# DoorCard.net
KiCad netlist of a schematic drawn in Altium Designer
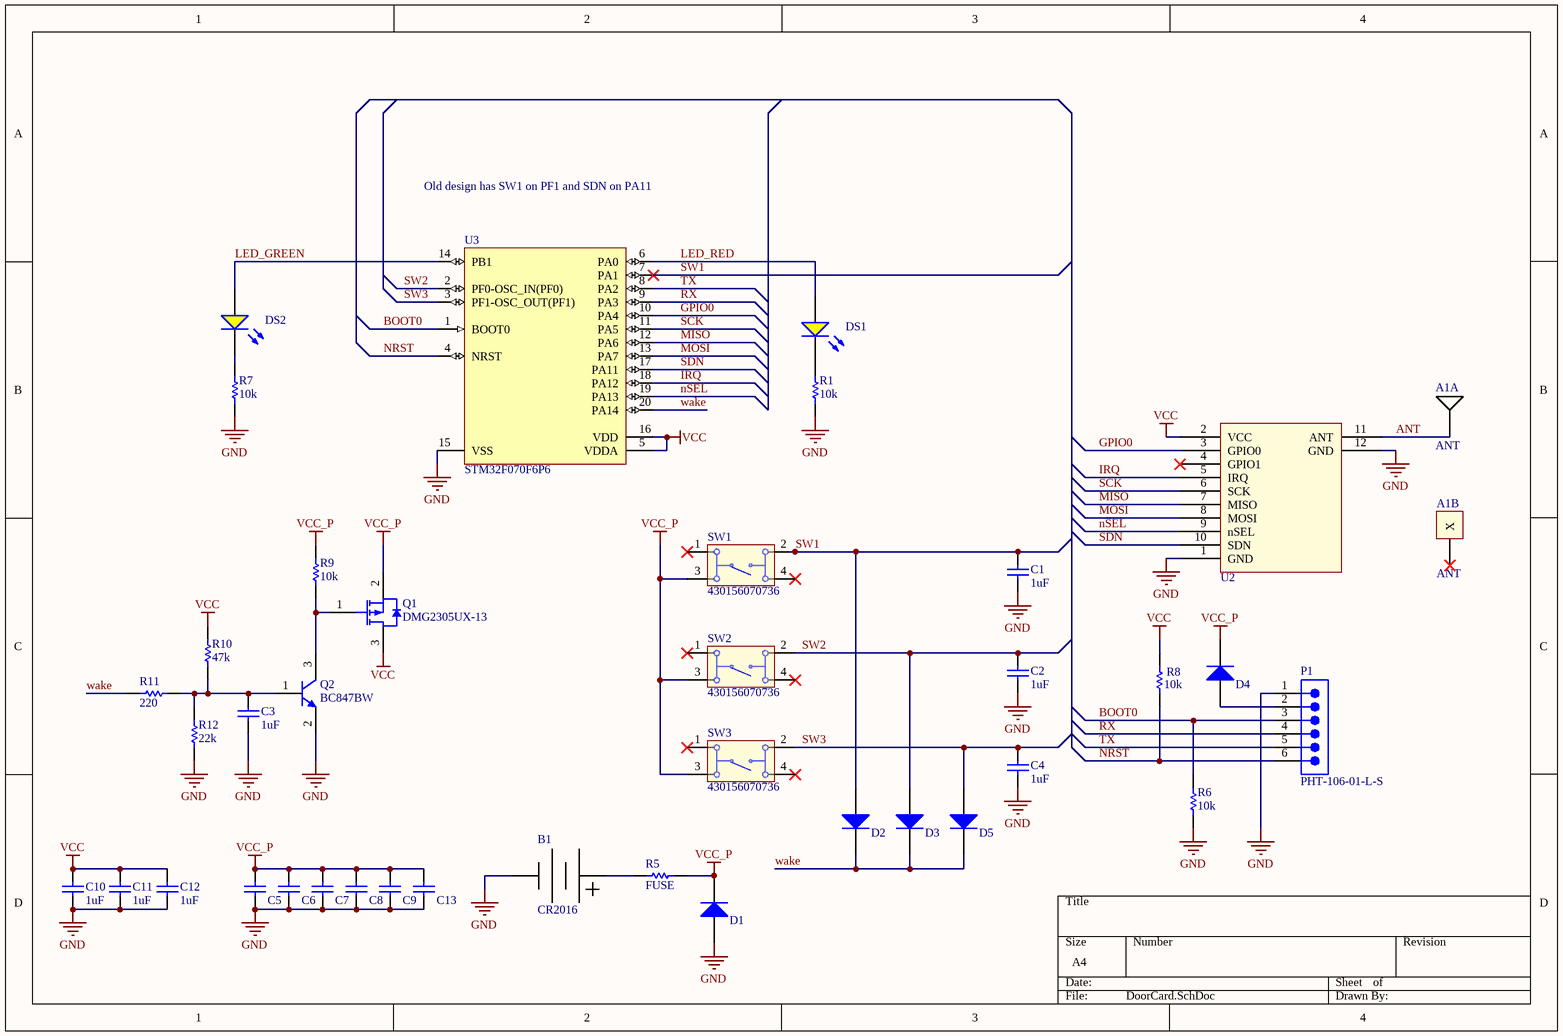
[diagram p0: DoorCard.SchDoc]

(export (version "E")
  (design (tool "Eeschema 10.0.6"))
  (components
    (comp (ref "A1")
      (value "ANT")
      (footprint "433MHz_Antenna")
      (description "ANT1204F002R0433A")
      (libsource (lib "Antenna") (part "ANT1204F002R0433A"))
    )
    (comp (ref "B1")
      (value "CR2016")
      (footprint "CR2012")
      (description "BAT-HLD-002-SMT")
      (libsource (lib "Cell") (part "BAT-HLD-002-SMT"))
    )
    (comp (ref "C1")
      (value "1uF")
      (footprint "CAPC0805(2012)100_M")
      (description "CAP 1uF 25V ±10% 0805 (2012 Metric) Thickness 1mm SMD")
      (fields (field (name "TOLERANCE") "Â±10%"))
      (libsource (lib "Altium Content Vault") (part "CAP"))
    )
    (comp (ref "C2")
      (value "1uF")
      (footprint "CAPC0805(2012)100_M")
      (description "CAP 1uF 25V ±10% 0805 (2012 Metric) Thickness 1mm SMD")
      (fields (field (name "TOLERANCE") "Â±10%"))
      (libsource (lib "Altium Content Vault") (part "CAP"))
    )
    (comp (ref "C3")
      (value "1uF")
      (footprint "CAPC0805(2012)100_M")
      (description "CAP 1uF 25V ±10% 0805 (2012 Metric) Thickness 1mm SMD")
      (fields (field (name "TOLERANCE") "Â±10%"))
      (libsource (lib "Altium Content Vault") (part "CAP"))
    )
    (comp (ref "C4")
      (value "1uF")
      (footprint "CAPC0805(2012)100_M")
      (description "CAP 1uF 25V ±10% 0805 (2012 Metric) Thickness 1mm SMD")
      (fields (field (name "TOLERANCE") "Â±10%"))
      (libsource (lib "Altium Content Vault") (part "CAP"))
    )
    (comp (ref "C5")
      (value "CAP 47uF 6.3V 1206(3216)")
      (footprint "CAPC1206(3216)190_M")
      (description "CAP 47uF 6.3V ±20% 1206 (3216 Metric) Thickness 1.9mm SMD")
      (fields (field (name "TOLERANCE") "Â±20%"))
      (libsource (lib "Altium Content Vault") (part "CMP-1037-05000-1"))
    )
    (comp (ref "C6")
      (value "CAP 47uF 6.3V 1206(3216)")
      (footprint "CAPC1206(3216)190_M")
      (description "CAP 47uF 6.3V ±20% 1206 (3216 Metric) Thickness 1.9mm SMD")
      (fields (field (name "TOLERANCE") "Â±20%"))
      (libsource (lib "Altium Content Vault") (part "CMP-1037-05000-1"))
    )
    (comp (ref "C7")
      (value "CAP 47uF 6.3V 1206(3216)")
      (footprint "CAPC1206(3216)190_M")
      (description "CAP 47uF 6.3V ±20% 1206 (3216 Metric) Thickness 1.9mm SMD")
      (fields (field (name "TOLERANCE") "Â±20%"))
      (libsource (lib "Altium Content Vault") (part "CMP-1037-05000-1"))
    )
    (comp (ref "C8")
      (value "CAP 47uF 6.3V 1206(3216)")
      (footprint "CAPC1206(3216)190_M")
      (description "CAP 47uF 6.3V ±20% 1206 (3216 Metric) Thickness 1.9mm SMD")
      (fields (field (name "TOLERANCE") "Â±20%"))
      (libsource (lib "Altium Content Vault") (part "CMP-1037-05000-1"))
    )
    (comp (ref "C9")
      (value "CAP 47uF 6.3V 1206(3216)")
      (footprint "CAPC1206(3216)190_M")
      (description "CAP 47uF 6.3V ±20% 1206 (3216 Metric) Thickness 1.9mm SMD")
      (fields (field (name "TOLERANCE") "Â±20%"))
      (libsource (lib "Altium Content Vault") (part "CMP-1037-05000-1"))
    )
    (comp (ref "C10")
      (value "1uF")
      (footprint "CAPC0805(2012)100_M")
      (description "CAP 1uF 25V ±10% 0805 (2012 Metric) Thickness 1mm SMD")
      (fields (field (name "TOLERANCE") "Â±10%"))
      (libsource (lib "Altium Content Vault") (part "CAP"))
    )
    (comp (ref "C11")
      (value "1uF")
      (footprint "CAPC0805(2012)100_M")
      (description "CAP 1uF 25V ±10% 0805 (2012 Metric) Thickness 1mm SMD")
      (fields (field (name "TOLERANCE") "Â±10%"))
      (libsource (lib "Altium Content Vault") (part "CAP"))
    )
    (comp (ref "C12")
      (value "1uF")
      (footprint "CAPC0805(2012)100_M")
      (description "CAP 1uF 25V ±10% 0805 (2012 Metric) Thickness 1mm SMD")
      (fields (field (name "TOLERANCE") "Â±10%"))
      (libsource (lib "Altium Content Vault") (part "CAP"))
    )
    (comp (ref "C13")
      (value "CAP 47uF 6.3V 1206(3216)")
      (footprint "CAPC1206(3216)190_M")
      (description "CAP 47uF 6.3V ±20% 1206 (3216 Metric) Thickness 1.9mm SMD")
      (fields (field (name "TOLERANCE") "Â±20%"))
      (libsource (lib "Altium Content Vault") (part "CMP-1037-05000-1"))
    )
    (comp (ref "D1")
      (value "MMSD4148T3G")
      (footprint "ONSC-SOD123-2-425G-04_V")
      (description "Switching Diode, 100 V, 200 mA, -55 to 150 degC, 2-Pin SOD123 (425), RoHS, Tape and Reel")
      (fields (field (name "MANUFACTURER") "ON Semiconductor"))
      (libsource (lib "Altium Content Vault") (part "ONSC-MMSD4148-SOD123-2"))
    )
    (comp (ref "D2")
      (value "MMSD4148T3G")
      (footprint "ONSC-SOD123-2-425G-04_V")
      (description "Switching Diode, 100 V, 200 mA, -55 to 150 degC, 2-Pin SOD123 (425), RoHS, Tape and Reel")
      (fields (field (name "MANUFACTURER") "ON Semiconductor"))
      (libsource (lib "Altium Content Vault") (part "ONSC-MMSD4148-SOD123-2"))
    )
    (comp (ref "D3")
      (value "MMSD4148T3G")
      (footprint "ONSC-SOD123-2-425G-04_V")
      (description "Switching Diode, 100 V, 200 mA, -55 to 150 degC, 2-Pin SOD123 (425), RoHS, Tape and Reel")
      (fields (field (name "MANUFACTURER") "ON Semiconductor"))
      (libsource (lib "Altium Content Vault") (part "ONSC-MMSD4148-SOD123-2"))
    )
    (comp (ref "D4")
      (value "MMSD4148T3G")
      (footprint "ONSC-SOD123-2-425G-04_V")
      (description "Switching Diode, 100 V, 200 mA, -55 to 150 degC, 2-Pin SOD123 (425), RoHS, Tape and Reel")
      (fields (field (name "MANUFACTURER") "ON Semiconductor"))
      (libsource (lib "Altium Content Vault") (part "ONSC-MMSD4148-SOD123-2"))
    )
    (comp (ref "D5")
      (value "MMSD4148T3G")
      (footprint "ONSC-SOD123-2-425G-04_V")
      (description "Switching Diode, 100 V, 200 mA, -55 to 150 degC, 2-Pin SOD123 (425), RoHS, Tape and Reel")
      (fields (field (name "MANUFACTURER") "ON Semiconductor"))
      (libsource (lib "Altium Content Vault") (part "ONSC-MMSD4148-SOD123-2"))
    )
    (comp (ref "DS1")
      (value "LTST-C170YKT")
      (footprint "LTST-C170YKT_V")
      (description "LED YELLOW CLEAR 0805 SMD")
      (libsource (lib "Altium Content Vault") (part "LED_YELLOW_AC"))
    )
    (comp (ref "DS2")
      (value "LTST-C170YKT")
      (footprint "LTST-C170YKT_V")
      (description "LED YELLOW CLEAR 0805 SMD")
      (libsource (lib "Altium Content Vault") (part "LED_YELLOW_AC"))
    )
    (comp (ref "P1")
      (value "PHT-106-01-L-S")
      (footprint "SMTC-PHT-106-01-X-S")
      (description "Press Fit Header, Through-hole, Vertical, -55 to 125 degC, 2.54 mm Pitch, 6-Pin, Male, RoHS")
      (fields (field (name "MANUFACTURER") "Samtec"))
      (libsource (lib "Altium Content Vault") (part "SMTC-PHT-106-01-X-S"))
    )
    (comp (ref "Q1")
      (value "DMG2305UX-13")
      (footprint "FAIR-SOT23-3_V")
      (fields (field (name "TOLERANCE") "30ppm"))
      (libsource (lib "Altium Content Vault") (part "PEMOS-GSD-3"))
    )
    (comp (ref "Q2")
      (value "BC847BW")
      (footprint "INF-SOT323_N")
      (description "NPN Silicon AF Transistor, 45 V VCEO, 100 mA IC, SOT323, Reel, Green")
      (fields (field (name "MANUFACTURER") "Infineon"))
      (libsource (lib "Altium Content Vault") (part "INF-BJTNPN-BEC-3"))
    )
    (comp (ref "R1")
      (value "10k")
      (footprint "RESC0805(2012)_L")
      (description "10K2 0.125W 1% 0805 (2012 Metric)  SMD")
      (fields (field (name "TOLERANCE") "1 %") (field (name "POWER") "0.125 W"))
      (libsource (lib "Altium Content Vault") (part "RES"))
    )
    (comp (ref "R5")
      (value "FUSE")
      (footprint "RESC0805(2012)_L")
      (description "PTC Fuse")
      (fields (field (name "TOLERANCE") "1 %") (field (name "POWER") "0.125 W"))
      (libsource (lib "Altium Content Vault") (part "RES"))
    )
    (comp (ref "R6")
      (value "10k")
      (footprint "RESC0805(2012)_L")
      (description "10K2 0.125W 1% 0805 (2012 Metric)  SMD")
      (fields (field (name "TOLERANCE") "1 %") (field (name "POWER") "0.125 W"))
      (libsource (lib "Altium Content Vault") (part "RES"))
    )
    (comp (ref "R7")
      (value "10k")
      (footprint "RESC0805(2012)_L")
      (description "10K2 0.125W 1% 0805 (2012 Metric)  SMD")
      (fields (field (name "TOLERANCE") "1 %") (field (name "POWER") "0.125 W"))
      (libsource (lib "Altium Content Vault") (part "RES"))
    )
    (comp (ref "R8")
      (value "10k")
      (footprint "RESC0805(2012)_L")
      (description "10K2 0.125W 1% 0805 (2012 Metric)  SMD")
      (fields (field (name "TOLERANCE") "1 %") (field (name "POWER") "0.125 W"))
      (libsource (lib "Altium Content Vault") (part "RES"))
    )
    (comp (ref "R9")
      (value "10k")
      (footprint "RESC0805(2012)_L")
      (description "10K2 0.125W 1% 0805 (2012 Metric)  SMD")
      (fields (field (name "TOLERANCE") "1 %") (field (name "POWER") "0.125 W"))
      (libsource (lib "Altium Content Vault") (part "RES"))
    )
    (comp (ref "R10")
      (value "47k")
      (footprint "RESC0805(2012)_L")
      (description "10K2 0.125W 1% 0805 (2012 Metric)  SMD")
      (fields (field (name "TOLERANCE") "1 %") (field (name "POWER") "0.125 W"))
      (libsource (lib "Altium Content Vault") (part "RES"))
    )
    (comp (ref "R11")
      (value "220")
      (footprint "RESC0805(2012)_L")
      (description "10K2 0.125W 1% 0805 (2012 Metric)  SMD")
      (fields (field (name "TOLERANCE") "1 %") (field (name "POWER") "0.125 W"))
      (libsource (lib "Altium Content Vault") (part "RES"))
    )
    (comp (ref "R12")
      (value "22k")
      (footprint "RESC0805(2012)_L")
      (description "10K2 0.125W 1% 0805 (2012 Metric)  SMD")
      (fields (field (name "TOLERANCE") "1 %") (field (name "POWER") "0.125 W"))
      (libsource (lib "Altium Content Vault") (part "RES"))
    )
    (comp (ref "SW1")
      (value "430156070736")
      (footprint "430156070736")
      (description "WS-TATV THT Tact Switch 6X6 mm")
      (fields (field (name "MANUFACTURER") "Wuerth Elektronik"))
      (libsource (lib "Altium Content Vault") (part "WE-TACT-SW-4"))
    )
    (comp (ref "SW2")
      (value "430156070736")
      (footprint "430156070736")
      (description "WS-TATV THT Tact Switch 6X6 mm")
      (fields (field (name "MANUFACTURER") "Wuerth Elektronik"))
      (libsource (lib "Altium Content Vault") (part "WE-TACT-SW-4"))
    )
    (comp (ref "SW3")
      (value "430156070736")
      (footprint "430156070736")
      (description "WS-TATV THT Tact Switch 6X6 mm")
      (fields (field (name "MANUFACTURER") "Wuerth Elektronik"))
      (libsource (lib "Altium Content Vault") (part "WE-TACT-SW-4"))
    )
    (comp (ref "U2")
      (value "Si4463")
      (footprint "E10-433MS")
      (description "E10-433MS")
      (libsource (lib "SiliconLabs") (part "Component_1"))
    )
    (comp (ref "U3")
      (value "STM32F070F6P6")
      (footprint "STM-TSSOP20_M")
      (fields (field (name "MANUFACTURER") "STMicroelectronics"))
      (libsource (lib "Altium Content Vault") (part "MC-ARM-STM32F070-TSSOP20"))
    )
  )
  (nets
    (net (code "1") (name "/ANT") (class "Default")
      (node (ref "A1") (pin "1") (pinfunction "ANT_1") (pintype "passive"))
      (node (ref "U2") (pin "11") (pinfunction "ANT_11") (pintype "passive"))
    )
    (net (code "2") (name "/BOOT0") (class "Default")
      (node (ref "P1") (pin "3") (pinfunction "3_3") (pintype "passive"))
      (node (ref "R6") (pin "2") (pinfunction "2_2") (pintype "passive"))
      (node (ref "U3") (pin "1") (pinfunction "BOOT0_1") (pintype "input"))
    )
    (net (code "3") (name "/GPIO0") (class "Default")
      (node (ref "U2") (pin "3") (pinfunction "GPIO0_3") (pintype "passive"))
      (node (ref "U3") (pin "10") (pinfunction "PA4_10") (pintype "bidirectional"))
    )
    (net (code "4") (name "/IRQ") (class "Default")
      (node (ref "U2") (pin "5") (pinfunction "IRQ_5") (pintype "passive"))
      (node (ref "U3") (pin "18") (pinfunction "PA12_18") (pintype "bidirectional"))
    )
    (net (code "5") (name "/LED_GREEN") (class "Default")
      (node (ref "DS2") (pin "A") (pinfunction "A_A") (pintype "passive"))
      (node (ref "U3") (pin "14") (pinfunction "PB1_14") (pintype "bidirectional"))
    )
    (net (code "6") (name "/LED_RED") (class "Default")
      (node (ref "DS1") (pin "A") (pinfunction "A_A") (pintype "passive"))
      (node (ref "U3") (pin "6") (pinfunction "PA0_6") (pintype "bidirectional"))
    )
    (net (code "7") (name "/MISO") (class "Default")
      (node (ref "U2") (pin "7") (pinfunction "MISO_7") (pintype "passive"))
      (node (ref "U3") (pin "12") (pinfunction "PA6_12") (pintype "bidirectional"))
    )
    (net (code "8") (name "/MOSI") (class "Default")
      (node (ref "U2") (pin "8") (pinfunction "MOSI_8") (pintype "passive"))
      (node (ref "U3") (pin "13") (pinfunction "PA7_13") (pintype "bidirectional"))
    )
    (net (code "9") (name "/NRST") (class "Default")
      (node (ref "P1") (pin "6") (pinfunction "6_6") (pintype "passive"))
      (node (ref "R8") (pin "1") (pinfunction "1_1") (pintype "passive"))
      (node (ref "U3") (pin "4") (pinfunction "NRST_4") (pintype "bidirectional"))
    )
    (net (code "10") (name "/RX") (class "Default")
      (node (ref "P1") (pin "4") (pinfunction "4_4") (pintype "passive"))
      (node (ref "U3") (pin "9") (pinfunction "PA3_9") (pintype "bidirectional"))
    )
    (net (code "11") (name "/SCK") (class "Default")
      (node (ref "U2") (pin "6") (pinfunction "SCK_6") (pintype "passive"))
      (node (ref "U3") (pin "11") (pinfunction "PA5_11") (pintype "bidirectional"))
    )
    (net (code "12") (name "/SDN") (class "Default")
      (node (ref "U2") (pin "10") (pinfunction "SDN_10") (pintype "passive"))
      (node (ref "U3") (pin "17") (pinfunction "PA11_17") (pintype "bidirectional"))
    )
    (net (code "13") (name "/SW1") (class "Default")
      (node (ref "C1") (pin "2") (pinfunction "2_2") (pintype "passive"))
      (node (ref "D2") (pin "2") (pinfunction "ANODE_2") (pintype "passive"))
      (node (ref "SW1") (pin "2") (pinfunction "2_2") (pintype "passive"))
      (node (ref "U3") (pin "7") (pinfunction "PA1_7") (pintype "bidirectional"))
    )
    (net (code "14") (name "/SW2") (class "Default")
      (node (ref "C2") (pin "2") (pinfunction "2_2") (pintype "passive"))
      (node (ref "D3") (pin "2") (pinfunction "ANODE_2") (pintype "passive"))
      (node (ref "SW2") (pin "2") (pinfunction "2_2") (pintype "passive"))
      (node (ref "U3") (pin "2") (pinfunction "PF0-OSC_IN(PF0)_2") (pintype "bidirectional"))
    )
    (net (code "15") (name "/SW3") (class "Default")
      (node (ref "C4") (pin "2") (pinfunction "2_2") (pintype "passive"))
      (node (ref "D5") (pin "2") (pinfunction "ANODE_2") (pintype "passive"))
      (node (ref "SW3") (pin "2") (pinfunction "2_2") (pintype "passive"))
      (node (ref "U3") (pin "3") (pinfunction "PF1-OSC_OUT(PF1)_3") (pintype "bidirectional"))
    )
    (net (code "16") (name "/TX") (class "Default")
      (node (ref "P1") (pin "5") (pinfunction "5_5") (pintype "passive"))
      (node (ref "U3") (pin "8") (pinfunction "PA2_8") (pintype "bidirectional"))
    )
    (net (code "17") (name "/nSEL") (class "Default")
      (node (ref "U2") (pin "9") (pinfunction "nSEL_9") (pintype "passive"))
      (node (ref "U3") (pin "19") (pinfunction "PA13_19") (pintype "bidirectional"))
    )
    (net (code "18") (name "/wake") (class "Default")
      (node (ref "D2") (pin "1") (pinfunction "CATHODE_1") (pintype "passive"))
      (node (ref "D3") (pin "1") (pinfunction "CATHODE_1") (pintype "passive"))
      (node (ref "D5") (pin "1") (pinfunction "CATHODE_1") (pintype "passive"))
      (node (ref "R11") (pin "2") (pinfunction "2_2") (pintype "passive"))
      (node (ref "U3") (pin "20") (pinfunction "PA14_20") (pintype "bidirectional"))
    )
    (net (code "19") (name "GND") (class "Default")
      (node (ref "B1") (pin "2") (pinfunction "2_2") (pintype "passive"))
      (node (ref "C1") (pin "1") (pinfunction "1_1") (pintype "passive"))
      (node (ref "C10") (pin "1") (pinfunction "1_1") (pintype "passive"))
      (node (ref "C11") (pin "1") (pinfunction "1_1") (pintype "passive"))
      (node (ref "C12") (pin "1") (pinfunction "1_1") (pintype "passive"))
      (node (ref "C13") (pin "1") (pinfunction "1_1") (pintype "passive"))
      (node (ref "C2") (pin "1") (pinfunction "1_1") (pintype "passive"))
      (node (ref "C3") (pin "1") (pinfunction "1_1") (pintype "passive"))
      (node (ref "C4") (pin "1") (pinfunction "1_1") (pintype "passive"))
      (node (ref "C5") (pin "1") (pinfunction "1_1") (pintype "passive"))
      (node (ref "C6") (pin "1") (pinfunction "1_1") (pintype "passive"))
      (node (ref "C7") (pin "1") (pinfunction "1_1") (pintype "passive"))
      (node (ref "C8") (pin "1") (pinfunction "1_1") (pintype "passive"))
      (node (ref "C9") (pin "1") (pinfunction "1_1") (pintype "passive"))
      (node (ref "D1") (pin "2") (pinfunction "ANODE_2") (pintype "passive"))
      (node (ref "P1") (pin "1") (pinfunction "1_1") (pintype "passive"))
      (node (ref "Q2") (pin "2") (pinfunction "E_2") (pintype "passive"))
      (node (ref "R1") (pin "1") (pinfunction "1_1") (pintype "passive"))
      (node (ref "R12") (pin "1") (pinfunction "1_1") (pintype "passive"))
      (node (ref "R6") (pin "1") (pinfunction "1_1") (pintype "passive"))
      (node (ref "R7") (pin "1") (pinfunction "1_1") (pintype "passive"))
      (node (ref "U2") (pin "1") (pinfunction "GND_1") (pintype "passive"))
      (node (ref "U2") (pin "12") (pinfunction "GND_12") (pintype "passive"))
      (node (ref "U3") (pin "15") (pinfunction "VSS_15") (pintype "power_in"))
    )
    (net (code "20") (name "Net-(B1-Pad1)") (class "Default")
      (node (ref "B1") (pin "1") (pinfunction "1_1") (pintype "passive"))
      (node (ref "R5") (pin "2") (pinfunction "2_2") (pintype "passive"))
    )
    (net (code "21") (name "Net-(D4-ANODE)") (class "Default")
      (node (ref "D4") (pin "2") (pinfunction "ANODE_2") (pintype "passive"))
      (node (ref "P1") (pin "2") (pinfunction "2_2") (pintype "passive"))
    )
    (net (code "22") (name "Net-(DS1-PadC)") (class "Default")
      (node (ref "DS1") (pin "C") (pinfunction "C_C") (pintype "passive"))
      (node (ref "R1") (pin "2") (pinfunction "2_2") (pintype "passive"))
    )
    (net (code "23") (name "Net-(DS2-PadC)") (class "Default")
      (node (ref "DS2") (pin "C") (pinfunction "C_C") (pintype "passive"))
      (node (ref "R7") (pin "2") (pinfunction "2_2") (pintype "passive"))
    )
    (net (code "24") (name "Net-(Q1-GATE)") (class "Default")
      (node (ref "Q1") (pin "1") (pinfunction "GATE_1") (pintype "passive"))
      (node (ref "Q2") (pin "3") (pinfunction "C_3") (pintype "passive"))
      (node (ref "R9") (pin "1") (pinfunction "1_1") (pintype "passive"))
    )
    (net (code "25") (name "Net-(Q2-B)") (class "Default")
      (node (ref "C3") (pin "2") (pinfunction "2_2") (pintype "passive"))
      (node (ref "Q2") (pin "1") (pinfunction "B_1") (pintype "passive"))
      (node (ref "R10") (pin "1") (pinfunction "1_1") (pintype "passive"))
      (node (ref "R11") (pin "1") (pinfunction "1_1") (pintype "passive"))
      (node (ref "R12") (pin "2") (pinfunction "2_2") (pintype "passive"))
    )
    (net (code "26") (name "VCC") (class "Default")
      (node (ref "C10") (pin "2") (pinfunction "2_2") (pintype "passive"))
      (node (ref "C11") (pin "2") (pinfunction "2_2") (pintype "passive"))
      (node (ref "C12") (pin "2") (pinfunction "2_2") (pintype "passive"))
      (node (ref "Q1") (pin "3") (pinfunction "DRAIN_3") (pintype "passive"))
      (node (ref "R10") (pin "2") (pinfunction "2_2") (pintype "passive"))
      (node (ref "R8") (pin "2") (pinfunction "2_2") (pintype "passive"))
      (node (ref "U2") (pin "2") (pinfunction "VCC_2") (pintype "passive"))
      (node (ref "U3") (pin "16") (pinfunction "VDD_16") (pintype "power_in"))
      (node (ref "U3") (pin "5") (pinfunction "VDDA_5") (pintype "power_in"))
    )
    (net (code "27") (name "VCC_P") (class "Default")
      (node (ref "C13") (pin "2") (pinfunction "2_2") (pintype "passive"))
      (node (ref "C5") (pin "2") (pinfunction "2_2") (pintype "passive"))
      (node (ref "C6") (pin "2") (pinfunction "2_2") (pintype "passive"))
      (node (ref "C7") (pin "2") (pinfunction "2_2") (pintype "passive"))
      (node (ref "C8") (pin "2") (pinfunction "2_2") (pintype "passive"))
      (node (ref "C9") (pin "2") (pinfunction "2_2") (pintype "passive"))
      (node (ref "D1") (pin "1") (pinfunction "CATHODE_1") (pintype "passive"))
      (node (ref "D4") (pin "1") (pinfunction "CATHODE_1") (pintype "passive"))
      (node (ref "Q1") (pin "2") (pinfunction "SOURCE_2") (pintype "passive"))
      (node (ref "R5") (pin "1") (pinfunction "1_1") (pintype "passive"))
      (node (ref "R9") (pin "2") (pinfunction "2_2") (pintype "passive"))
      (node (ref "SW1") (pin "3") (pinfunction "3_3") (pintype "passive"))
      (node (ref "SW2") (pin "3") (pinfunction "3_3") (pintype "passive"))
      (node (ref "SW3") (pin "3") (pinfunction "3_3") (pintype "passive"))
    )
    (net (code "28") (name "unconnected-(A1B-X-Pad2)") (class "Default")
      (node (ref "A1") (pin "2") (pinfunction "X_2") (pintype "passive+no_connect"))
    )
    (net (code "29") (name "unconnected-(SW1-Pad1)") (class "Default")
      (node (ref "SW1") (pin "1") (pinfunction "1_1") (pintype "passive+no_connect"))
    )
    (net (code "30") (name "unconnected-(SW1-Pad4)") (class "Default")
      (node (ref "SW1") (pin "4") (pinfunction "4_4") (pintype "passive+no_connect"))
    )
    (net (code "31") (name "unconnected-(SW2-Pad1)") (class "Default")
      (node (ref "SW2") (pin "1") (pinfunction "1_1") (pintype "passive+no_connect"))
    )
    (net (code "32") (name "unconnected-(SW2-Pad4)") (class "Default")
      (node (ref "SW2") (pin "4") (pinfunction "4_4") (pintype "passive+no_connect"))
    )
    (net (code "33") (name "unconnected-(SW3-Pad1)") (class "Default")
      (node (ref "SW3") (pin "1") (pinfunction "1_1") (pintype "passive+no_connect"))
    )
    (net (code "34") (name "unconnected-(SW3-Pad4)") (class "Default")
      (node (ref "SW3") (pin "4") (pinfunction "4_4") (pintype "passive+no_connect"))
    )
    (net (code "35") (name "unconnected-(U2-GPIO1-Pad4)") (class "Default")
      (node (ref "U2") (pin "4") (pinfunction "GPIO1_4") (pintype "passive+no_connect"))
    )
  )
)
